# 1-Schematic_Final_project.net
KiCad netlist of a schematic drawn in EasyEDA
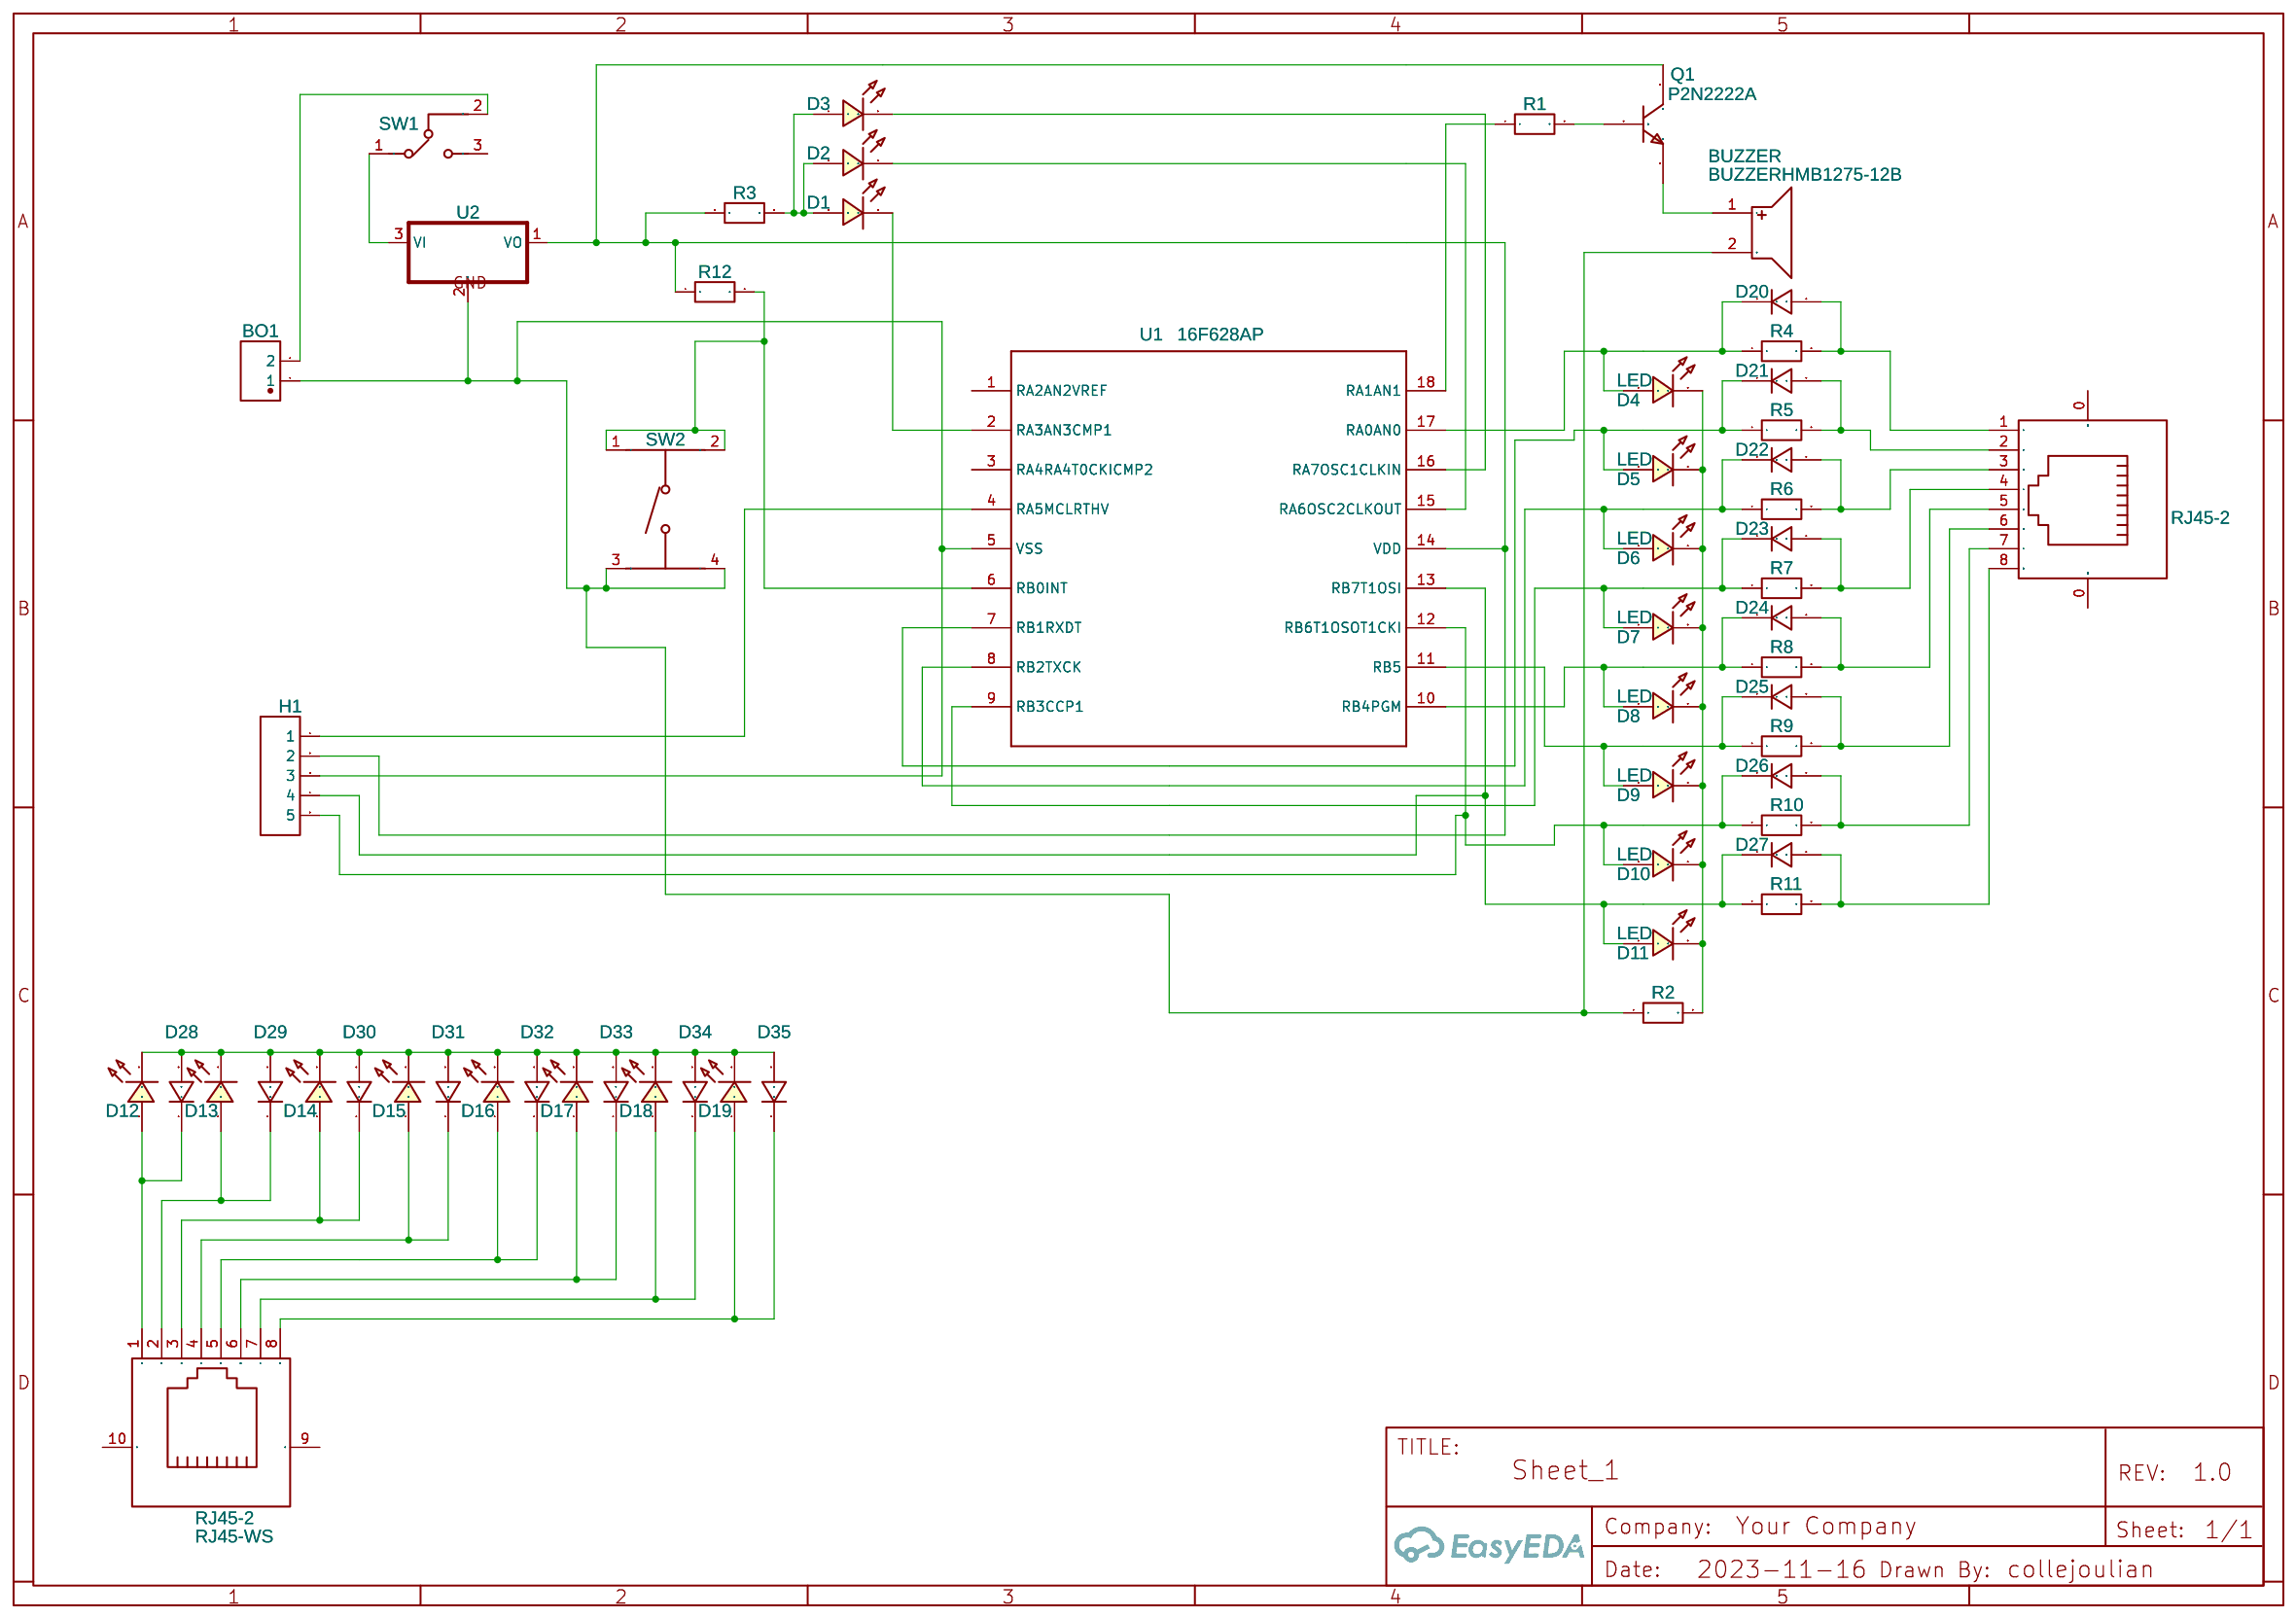
[diagram p0: schematic sheet]

(export (version "E")
  (design (tool "Eeschema 10.0.6"))
  (components
    (comp (ref "BO1")
      (value "BV-2P-5mm")
      (fields
        (field (name "Manufacturer Part") "KF301-5.0-2P")
        (field (name "Manufacturer") "Cixi Kefa Elec")
      )
      (libsource (lib "") (part "Bornier A Vis 2P - 5mm"))
    )
    (comp (ref "BUZZER")
      (value "BUZZERHMB1275-12B")
      (fields (field (name "Manufacturer Part") "buzzerHMB1275-12B") (field (name "Manufacturer") "HNDZ"))
      (libsource (lib "") (part "BUZZERHMB1275-12B"))
    )
    (comp (ref "D1")
      (value "D1")
      (fields
        (field (name "Manufacturer Part") "204-10SDRD/S530-A3-L")
        (field (name "Manufacturer") "EVERLIGHT(台湾亿光)")
      )
      (libsource (lib "") (part "LED-TH-3mm_R_1"))
    )
    (comp (ref "D2")
      (value "D2")
      (fields
        (field (name "Manufacturer Part") "204-10SDRD/S530-A3-L")
        (field (name "Manufacturer") "EVERLIGHT(台湾亿光)")
      )
      (libsource (lib "") (part "LED-TH-3mm_R_1"))
    )
    (comp (ref "D3")
      (value "D3")
      (fields
        (field (name "Manufacturer Part") "204-10SDRD/S530-A3-L")
        (field (name "Manufacturer") "EVERLIGHT(台湾亿光)")
      )
      (libsource (lib "") (part "LED-TH-3mm_R_1"))
    )
    (comp (ref "D4")
      (value "LED")
      (fields
        (field (name "Manufacturer Part") "204-10SDRD/S530-A3-L")
        (field (name "Manufacturer") "EVERLIGHT(台湾亿光)")
      )
      (libsource (lib "") (part "LED-TH-3mm_R_1"))
    )
    (comp (ref "D5")
      (value "LED")
      (fields
        (field (name "Manufacturer Part") "204-10SDRD/S530-A3-L")
        (field (name "Manufacturer") "EVERLIGHT(台湾亿光)")
      )
      (libsource (lib "") (part "LED-TH-3mm_R_1"))
    )
    (comp (ref "D6")
      (value "LED")
      (fields
        (field (name "Manufacturer Part") "204-10SDRD/S530-A3-L")
        (field (name "Manufacturer") "EVERLIGHT(台湾亿光)")
      )
      (libsource (lib "") (part "LED-TH-3mm_R_1"))
    )
    (comp (ref "D7")
      (value "LED")
      (fields
        (field (name "Manufacturer Part") "204-10SDRD/S530-A3-L")
        (field (name "Manufacturer") "EVERLIGHT(台湾亿光)")
      )
      (libsource (lib "") (part "LED-TH-3mm_R_1"))
    )
    (comp (ref "D8")
      (value "LED")
      (fields
        (field (name "Manufacturer Part") "204-10SDRD/S530-A3-L")
        (field (name "Manufacturer") "EVERLIGHT(台湾亿光)")
      )
      (libsource (lib "") (part "LED-TH-3mm_R_1"))
    )
    (comp (ref "D9")
      (value "LED")
      (fields
        (field (name "Manufacturer Part") "204-10SDRD/S530-A3-L")
        (field (name "Manufacturer") "EVERLIGHT(台湾亿光)")
      )
      (libsource (lib "") (part "LED-TH-3mm_R_1"))
    )
    (comp (ref "D10")
      (value "LED")
      (fields
        (field (name "Manufacturer Part") "204-10SDRD/S530-A3-L")
        (field (name "Manufacturer") "EVERLIGHT(台湾亿光)")
      )
      (libsource (lib "") (part "LED-TH-3mm_R_1"))
    )
    (comp (ref "D11")
      (value "LED")
      (fields
        (field (name "Manufacturer Part") "204-10SDRD/S530-A3-L")
        (field (name "Manufacturer") "EVERLIGHT(台湾亿光)")
      )
      (libsource (lib "") (part "LED-TH-3mm_R_1"))
    )
    (comp (ref "D12")
      (value "D12")
      (fields
        (field (name "Manufacturer Part") "204-10SDRD/S530-A3-L")
        (field (name "Manufacturer") "EVERLIGHT(台湾亿光)")
      )
      (libsource (lib "") (part "LED-TH-3mm_R"))
    )
    (comp (ref "D13")
      (value "D13")
      (fields
        (field (name "Manufacturer Part") "204-10SDRD/S530-A3-L")
        (field (name "Manufacturer") "EVERLIGHT(台湾亿光)")
      )
      (libsource (lib "") (part "LED-TH-3mm_R"))
    )
    (comp (ref "D14")
      (value "D14")
      (fields
        (field (name "Manufacturer Part") "204-10SDRD/S530-A3-L")
        (field (name "Manufacturer") "EVERLIGHT(台湾亿光)")
      )
      (libsource (lib "") (part "LED-TH-3mm_R"))
    )
    (comp (ref "D15")
      (value "D15")
      (fields
        (field (name "Manufacturer Part") "204-10SDRD/S530-A3-L")
        (field (name "Manufacturer") "EVERLIGHT(台湾亿光)")
      )
      (libsource (lib "") (part "LED-TH-3mm_R"))
    )
    (comp (ref "D16")
      (value "D16")
      (fields
        (field (name "Manufacturer Part") "204-10SDRD/S530-A3-L")
        (field (name "Manufacturer") "EVERLIGHT(台湾亿光)")
      )
      (libsource (lib "") (part "LED-TH-3mm_R"))
    )
    (comp (ref "D17")
      (value "D17")
      (fields
        (field (name "Manufacturer Part") "204-10SDRD/S530-A3-L")
        (field (name "Manufacturer") "EVERLIGHT(台湾亿光)")
      )
      (libsource (lib "") (part "LED-TH-3mm_R"))
    )
    (comp (ref "D18")
      (value "D18")
      (fields
        (field (name "Manufacturer Part") "204-10SDRD/S530-A3-L")
        (field (name "Manufacturer") "EVERLIGHT(台湾亿光)")
      )
      (libsource (lib "") (part "LED-TH-3mm_R"))
    )
    (comp (ref "D19")
      (value "D19")
      (fields
        (field (name "Manufacturer Part") "204-10SDRD/S530-A3-L")
        (field (name "Manufacturer") "EVERLIGHT(台湾亿光)")
      )
      (libsource (lib "") (part "LED-TH-3mm_R"))
    )
    (comp (ref "D20")
      (value "D")
      (fields (field (name "Manufacturer Part") "1N4148") (field (name "Manufacturer") "STMicroelectronics"))
      (libsource (lib "") (part "1N4148"))
    )
    (comp (ref "D21")
      (value "D")
      (fields (field (name "Manufacturer Part") "1N4148") (field (name "Manufacturer") "STMicroelectronics"))
      (libsource (lib "") (part "1N4148"))
    )
    (comp (ref "D22")
      (value "D")
      (fields (field (name "Manufacturer Part") "1N4148") (field (name "Manufacturer") "STMicroelectronics"))
      (libsource (lib "") (part "1N4148"))
    )
    (comp (ref "D23")
      (value "D")
      (fields (field (name "Manufacturer Part") "1N4148") (field (name "Manufacturer") "STMicroelectronics"))
      (libsource (lib "") (part "1N4148"))
    )
    (comp (ref "D24")
      (value "D")
      (fields (field (name "Manufacturer Part") "1N4148") (field (name "Manufacturer") "STMicroelectronics"))
      (libsource (lib "") (part "1N4148"))
    )
    (comp (ref "D25")
      (value "D")
      (fields (field (name "Manufacturer Part") "1N4148") (field (name "Manufacturer") "STMicroelectronics"))
      (libsource (lib "") (part "1N4148"))
    )
    (comp (ref "D26")
      (value "D")
      (fields (field (name "Manufacturer Part") "1N4148") (field (name "Manufacturer") "STMicroelectronics"))
      (libsource (lib "") (part "1N4148"))
    )
    (comp (ref "D27")
      (value "D")
      (fields (field (name "Manufacturer Part") "1N4148") (field (name "Manufacturer") "STMicroelectronics"))
      (libsource (lib "") (part "1N4148"))
    )
    (comp (ref "D28")
      (value "D28")
      (fields (field (name "Manufacturer Part") "1N4148") (field (name "Manufacturer") "STMicroelectronics"))
      (libsource (lib "") (part "1N4148_1"))
    )
    (comp (ref "D29")
      (value "D29")
      (fields (field (name "Manufacturer Part") "1N4148") (field (name "Manufacturer") "STMicroelectronics"))
      (libsource (lib "") (part "1N4148_1"))
    )
    (comp (ref "D30")
      (value "D30")
      (fields (field (name "Manufacturer Part") "1N4148") (field (name "Manufacturer") "STMicroelectronics"))
      (libsource (lib "") (part "1N4148_1"))
    )
    (comp (ref "D31")
      (value "D31")
      (fields (field (name "Manufacturer Part") "1N4148") (field (name "Manufacturer") "STMicroelectronics"))
      (libsource (lib "") (part "1N4148_1"))
    )
    (comp (ref "D32")
      (value "D32")
      (fields (field (name "Manufacturer Part") "1N4148") (field (name "Manufacturer") "STMicroelectronics"))
      (libsource (lib "") (part "1N4148_1"))
    )
    (comp (ref "D33")
      (value "D33")
      (fields (field (name "Manufacturer Part") "1N4148") (field (name "Manufacturer") "STMicroelectronics"))
      (libsource (lib "") (part "1N4148_1"))
    )
    (comp (ref "D34")
      (value "D34")
      (fields (field (name "Manufacturer Part") "1N4148") (field (name "Manufacturer") "STMicroelectronics"))
      (libsource (lib "") (part "1N4148_1"))
    )
    (comp (ref "D35")
      (value "D35")
      (fields (field (name "Manufacturer Part") "1N4148") (field (name "Manufacturer") "STMicroelectronics"))
      (libsource (lib "") (part "1N4148_1"))
    )
    (comp (ref "H1")
      (value "1z2")
      (fields (field (name "Manufacturer Part") "2.54-1*5P母") (field (name "Manufacturer") "BOOMELE(博穆精密)"))
      (libsource (lib "") (part "Header-Female-2.54_1x5"))
    )
    (comp (ref "Q1") (value "P2N2222A") (libsource (lib "") (part "P2N2222A")))
    (comp (ref "R1") (value "1k") (libsource (lib "") (part "R_AXIAL-0.3_EU")))
    (comp (ref "R2") (value "1k") (libsource (lib "") (part "R_AXIAL-0.3_EU")))
    (comp (ref "R3") (value "1k") (libsource (lib "") (part "R_AXIAL-0.3_EU")))
    (comp (ref "R4") (value "1k") (libsource (lib "") (part "R_AXIAL-0.3_EU")))
    (comp (ref "R5") (value "1k") (libsource (lib "") (part "R_AXIAL-0.3_EU")))
    (comp (ref "R6") (value "1k") (libsource (lib "") (part "R_AXIAL-0.3_EU")))
    (comp (ref "R7") (value "1k") (libsource (lib "") (part "R_AXIAL-0.3_EU")))
    (comp (ref "R8") (value "1k") (libsource (lib "") (part "R_AXIAL-0.3_EU")))
    (comp (ref "R9") (value "1k") (libsource (lib "") (part "R_AXIAL-0.3_EU")))
    (comp (ref "R10") (value "1k") (libsource (lib "") (part "R_AXIAL-0.3_EU")))
    (comp (ref "R11") (value "1k") (libsource (lib "") (part "R_AXIAL-0.3_EU")))
    (comp (ref "R12") (value "1k") (libsource (lib "") (part "R_AXIAL-0.3_EU")))
    (comp (ref "RJ45")
      (value "RJ45-2")
      (fields (field (name "Manufacturer Part") "DS1128-04-S8B8P-X") (field (name "Manufacturer") "CONNFLY"))
      (libsource (lib "") (part "DS1128-04-S8B8P-X"))
    )
    (comp (ref "RJ45-2")
      (value "RJ45-WS")
      (fields
        (field (name "Manufacturer Part") "FRJ45004-1100K6K02C0")
        (field (name "Manufacturer") "TXGA(特思嘉)")
      )
      (libsource (lib "") (part "FRJ45004-1100K6K02C0"))
    )
    (comp (ref "SW1")
      (value "SW1")
      (fields (field (name "Manufacturer Part") "1101M2S3CQE2") (field (name "Manufacturer") "C&K"))
      (libsource (lib "") (part "1101M2S3CQE2"))
    )
    (comp (ref "SW2")
      (value "TS-1102-5016")
      (fields (field (name "Manufacturer") "SOFNG(硕方)"))
      (libsource (lib "") (part "TS-1102-5016"))
    )
    (comp (ref "U1") (value "16F628AP") (libsource (lib "") (part "16F628AP")))
    (comp (ref "U2") (value "7805L") (libsource (lib "") (part "7805L")))
  )
  (nets
    (net (code "1") (name "Net-(BO1-Pad2)") (class "Default")
      (node (ref "BO1") (pin "2") (pinfunction "2_2") (pintype "unspecified"))
      (node (ref "SW1") (pin "2") (pinfunction "2_2") (pintype "unspecified"))
    )
    (net (code "2") (name "Net-(D1-Pad1)") (class "Default")
      (node (ref "D1") (pin "1") (pinfunction "1_1") (pintype "unspecified"))
      (node (ref "D2") (pin "1") (pinfunction "1_1") (pintype "unspecified"))
      (node (ref "D3") (pin "1") (pinfunction "1_1") (pintype "unspecified"))
      (node (ref "R3") (pin "2") (pinfunction "2_2") (pintype "unspecified"))
    )
    (net (code "3") (name "Net-(D10-Pad2)") (class "Default")
      (node (ref "D10") (pin "2") (pinfunction "2_2") (pintype "unspecified"))
      (node (ref "D11") (pin "2") (pinfunction "2_2") (pintype "unspecified"))
      (node (ref "D4") (pin "2") (pinfunction "2_2") (pintype "unspecified"))
      (node (ref "D5") (pin "2") (pinfunction "2_2") (pintype "unspecified"))
      (node (ref "D6") (pin "2") (pinfunction "2_2") (pintype "unspecified"))
      (node (ref "D7") (pin "2") (pinfunction "2_2") (pintype "unspecified"))
      (node (ref "D8") (pin "2") (pinfunction "2_2") (pintype "unspecified"))
      (node (ref "D9") (pin "2") (pinfunction "2_2") (pintype "unspecified"))
      (node (ref "R2") (pin "2") (pinfunction "2_2") (pintype "unspecified"))
    )
    (net (code "4") (name "Net-(D12-Pad1)") (class "Default")
      (node (ref "D12") (pin "1") (pinfunction "1_1") (pintype "unspecified"))
      (node (ref "D28") (pin "1") (pinfunction "1_1") (pintype "unspecified"))
      (node (ref "RJ45-2") (pin "1") (pinfunction "1_1") (pintype "unspecified"))
    )
    (net (code "5") (name "Net-(D12-Pad2)") (class "Default")
      (node (ref "D12") (pin "2") (pinfunction "2_2") (pintype "unspecified"))
      (node (ref "D13") (pin "2") (pinfunction "2_2") (pintype "unspecified"))
      (node (ref "D14") (pin "2") (pinfunction "2_2") (pintype "unspecified"))
      (node (ref "D15") (pin "2") (pinfunction "2_2") (pintype "unspecified"))
      (node (ref "D16") (pin "2") (pinfunction "2_2") (pintype "unspecified"))
      (node (ref "D17") (pin "2") (pinfunction "2_2") (pintype "unspecified"))
      (node (ref "D18") (pin "2") (pinfunction "2_2") (pintype "unspecified"))
      (node (ref "D19") (pin "2") (pinfunction "2_2") (pintype "unspecified"))
      (node (ref "D28") (pin "2") (pinfunction "2_2") (pintype "unspecified"))
      (node (ref "D29") (pin "2") (pinfunction "2_2") (pintype "unspecified"))
      (node (ref "D30") (pin "2") (pinfunction "2_2") (pintype "unspecified"))
      (node (ref "D31") (pin "2") (pinfunction "2_2") (pintype "unspecified"))
      (node (ref "D32") (pin "2") (pinfunction "2_2") (pintype "unspecified"))
      (node (ref "D33") (pin "2") (pinfunction "2_2") (pintype "unspecified"))
      (node (ref "D34") (pin "2") (pinfunction "2_2") (pintype "unspecified"))
      (node (ref "D35") (pin "2") (pinfunction "2_2") (pintype "unspecified"))
    )
    (net (code "6") (name "Net-(D13-Pad1)") (class "Default")
      (node (ref "D13") (pin "1") (pinfunction "1_1") (pintype "unspecified"))
      (node (ref "D29") (pin "1") (pinfunction "1_1") (pintype "unspecified"))
      (node (ref "RJ45-2") (pin "2") (pinfunction "2_2") (pintype "unspecified"))
    )
    (net (code "7") (name "Net-(D14-Pad1)") (class "Default")
      (node (ref "D14") (pin "1") (pinfunction "1_1") (pintype "unspecified"))
      (node (ref "D30") (pin "1") (pinfunction "1_1") (pintype "unspecified"))
      (node (ref "RJ45-2") (pin "3") (pinfunction "3_3") (pintype "unspecified"))
    )
    (net (code "8") (name "Net-(D15-Pad1)") (class "Default")
      (node (ref "D15") (pin "1") (pinfunction "1_1") (pintype "unspecified"))
      (node (ref "D31") (pin "1") (pinfunction "1_1") (pintype "unspecified"))
      (node (ref "RJ45-2") (pin "4") (pinfunction "4_4") (pintype "unspecified"))
    )
    (net (code "9") (name "Net-(D16-Pad1)") (class "Default")
      (node (ref "D16") (pin "1") (pinfunction "1_1") (pintype "unspecified"))
      (node (ref "D32") (pin "1") (pinfunction "1_1") (pintype "unspecified"))
      (node (ref "RJ45-2") (pin "5") (pinfunction "5_5") (pintype "unspecified"))
    )
    (net (code "10") (name "Net-(D17-Pad1)") (class "Default")
      (node (ref "D17") (pin "1") (pinfunction "1_1") (pintype "unspecified"))
      (node (ref "D33") (pin "1") (pinfunction "1_1") (pintype "unspecified"))
      (node (ref "RJ45-2") (pin "6") (pinfunction "6_6") (pintype "unspecified"))
    )
    (net (code "11") (name "Net-(D18-Pad1)") (class "Default")
      (node (ref "D18") (pin "1") (pinfunction "1_1") (pintype "unspecified"))
      (node (ref "D34") (pin "1") (pinfunction "1_1") (pintype "unspecified"))
      (node (ref "RJ45-2") (pin "7") (pinfunction "7_7") (pintype "unspecified"))
    )
    (net (code "12") (name "Net-(D19-Pad1)") (class "Default")
      (node (ref "D19") (pin "1") (pinfunction "1_1") (pintype "unspecified"))
      (node (ref "D35") (pin "1") (pinfunction "1_1") (pintype "unspecified"))
      (node (ref "RJ45-2") (pin "8") (pinfunction "8_8") (pintype "unspecified"))
    )
    (net (code "13") (name "Net-(D20-Pad2)") (class "Default")
      (node (ref "D20") (pin "2") (pinfunction "2_2") (pintype "unspecified"))
      (node (ref "R4") (pin "2") (pinfunction "2_2") (pintype "unspecified"))
      (node (ref "RJ45") (pin "1") (pinfunction "1_1") (pintype "unspecified"))
    )
    (net (code "14") (name "Net-(D21-Pad2)") (class "Default")
      (node (ref "D21") (pin "2") (pinfunction "2_2") (pintype "unspecified"))
      (node (ref "R5") (pin "2") (pinfunction "2_2") (pintype "unspecified"))
      (node (ref "RJ45") (pin "2") (pinfunction "2_2") (pintype "unspecified"))
    )
    (net (code "15") (name "Net-(D22-Pad2)") (class "Default")
      (node (ref "D22") (pin "2") (pinfunction "2_2") (pintype "unspecified"))
      (node (ref "R6") (pin "2") (pinfunction "2_2") (pintype "unspecified"))
      (node (ref "RJ45") (pin "3") (pinfunction "3_3") (pintype "unspecified"))
    )
    (net (code "16") (name "Net-(D23-Pad2)") (class "Default")
      (node (ref "D23") (pin "2") (pinfunction "2_2") (pintype "unspecified"))
      (node (ref "R7") (pin "2") (pinfunction "2_2") (pintype "unspecified"))
      (node (ref "RJ45") (pin "4") (pinfunction "4_4") (pintype "unspecified"))
    )
    (net (code "17") (name "Net-(D24-Pad2)") (class "Default")
      (node (ref "D24") (pin "2") (pinfunction "2_2") (pintype "unspecified"))
      (node (ref "R8") (pin "2") (pinfunction "2_2") (pintype "unspecified"))
      (node (ref "RJ45") (pin "5") (pinfunction "5_5") (pintype "unspecified"))
    )
    (net (code "18") (name "Net-(D25-Pad2)") (class "Default")
      (node (ref "D25") (pin "2") (pinfunction "2_2") (pintype "unspecified"))
      (node (ref "R9") (pin "2") (pinfunction "2_2") (pintype "unspecified"))
      (node (ref "RJ45") (pin "6") (pinfunction "6_6") (pintype "unspecified"))
    )
    (net (code "19") (name "Net-(D26-Pad2)") (class "Default")
      (node (ref "D26") (pin "2") (pinfunction "2_2") (pintype "unspecified"))
      (node (ref "R10") (pin "2") (pinfunction "2_2") (pintype "unspecified"))
      (node (ref "RJ45") (pin "7") (pinfunction "7_7") (pintype "unspecified"))
    )
    (net (code "20") (name "Net-(D27-Pad2)") (class "Default")
      (node (ref "D27") (pin "2") (pinfunction "2_2") (pintype "unspecified"))
      (node (ref "R11") (pin "2") (pinfunction "2_2") (pintype "unspecified"))
      (node (ref "RJ45") (pin "8") (pinfunction "8_8") (pintype "unspecified"))
    )
    (net (code "21") (name "Net-(Q1-B)") (class "Default")
      (node (ref "Q1") (pin "2") (pinfunction "B_2") (pintype "unspecified"))
      (node (ref "R1") (pin "2") (pinfunction "2_2") (pintype "unspecified"))
    )
    (net (code "22") (name "Net-(Q1-C)") (class "Default")
      (node (ref "H1") (pin "2") (pinfunction "2_2") (pintype "input"))
      (node (ref "Q1") (pin "1") (pinfunction "C_1") (pintype "unspecified"))
      (node (ref "R12") (pin "1") (pinfunction "1_1") (pintype "unspecified"))
      (node (ref "R3") (pin "1") (pinfunction "1_1") (pintype "unspecified"))
      (node (ref "U1") (pin "14") (pinfunction "VDD_14") (pintype "passive"))
      (node (ref "U2") (pin "1") (pinfunction "VO_1") (pintype "unspecified"))
    )
    (net (code "23") (name "Net-(Q1-E)") (class "Default")
      (node (ref "BUZZER") (pin "1") (pinfunction "1_1") (pintype "unspecified"))
      (node (ref "Q1") (pin "3") (pinfunction "E_3") (pintype "unspecified"))
    )
    (net (code "24") (name "Net-(U1-RA0AN0)") (class "Default")
      (node (ref "D20") (pin "1") (pinfunction "1_1") (pintype "unspecified"))
      (node (ref "D4") (pin "1") (pinfunction "1_1") (pintype "unspecified"))
      (node (ref "R4") (pin "1") (pinfunction "1_1") (pintype "unspecified"))
      (node (ref "U1") (pin "17") (pinfunction "RA0AN0_17") (pintype "unspecified"))
    )
    (net (code "25") (name "Net-(U1-RA1AN1)") (class "Default")
      (node (ref "R1") (pin "1") (pinfunction "1_1") (pintype "unspecified"))
      (node (ref "U1") (pin "18") (pinfunction "RA1AN1_18") (pintype "unspecified"))
    )
    (net (code "26") (name "Net-(U1-RA3AN3CMP1)") (class "Default")
      (node (ref "D1") (pin "2") (pinfunction "2_2") (pintype "unspecified"))
      (node (ref "U1") (pin "2") (pinfunction "RA3AN3CMP1_2") (pintype "unspecified"))
    )
    (net (code "27") (name "Net-(U1-RA5MCLRTHV)") (class "Default")
      (node (ref "H1") (pin "1") (pinfunction "1_1") (pintype "input"))
      (node (ref "U1") (pin "4") (pinfunction "RA5MCLRTHV_4") (pintype "input"))
    )
    (net (code "28") (name "Net-(U1-RA6OSC2CLKOUT)") (class "Default")
      (node (ref "D2") (pin "2") (pinfunction "2_2") (pintype "unspecified"))
      (node (ref "U1") (pin "15") (pinfunction "RA6OSC2CLKOUT_15") (pintype "unspecified"))
    )
    (net (code "29") (name "Net-(U1-RA7OSC1CLKIN)") (class "Default")
      (node (ref "D3") (pin "2") (pinfunction "2_2") (pintype "unspecified"))
      (node (ref "U1") (pin "16") (pinfunction "RA7OSC1CLKIN_16") (pintype "unspecified"))
    )
    (net (code "30") (name "Net-(U1-RB0INT)") (class "Default")
      (node (ref "R12") (pin "2") (pinfunction "2_2") (pintype "unspecified"))
      (node (ref "SW2") (pin "1") (pinfunction "1_1") (pintype "unspecified"))
      (node (ref "SW2") (pin "2") (pinfunction "2_2") (pintype "unspecified"))
      (node (ref "U1") (pin "6") (pinfunction "RB0INT_6") (pintype "unspecified"))
    )
    (net (code "31") (name "Net-(U1-RB1RXDT)") (class "Default")
      (node (ref "D21") (pin "1") (pinfunction "1_1") (pintype "unspecified"))
      (node (ref "D5") (pin "1") (pinfunction "1_1") (pintype "unspecified"))
      (node (ref "R5") (pin "1") (pinfunction "1_1") (pintype "unspecified"))
      (node (ref "U1") (pin "7") (pinfunction "RB1RXDT_7") (pintype "unspecified"))
    )
    (net (code "32") (name "Net-(U1-RB2TXCK)") (class "Default")
      (node (ref "D22") (pin "1") (pinfunction "1_1") (pintype "unspecified"))
      (node (ref "D6") (pin "1") (pinfunction "1_1") (pintype "unspecified"))
      (node (ref "R6") (pin "1") (pinfunction "1_1") (pintype "unspecified"))
      (node (ref "U1") (pin "8") (pinfunction "RB2TXCK_8") (pintype "unspecified"))
    )
    (net (code "33") (name "Net-(U1-RB3CCP1)") (class "Default")
      (node (ref "D23") (pin "1") (pinfunction "1_1") (pintype "unspecified"))
      (node (ref "D7") (pin "1") (pinfunction "1_1") (pintype "unspecified"))
      (node (ref "R7") (pin "1") (pinfunction "1_1") (pintype "unspecified"))
      (node (ref "U1") (pin "9") (pinfunction "RB3CCP1_9") (pintype "unspecified"))
    )
    (net (code "34") (name "Net-(U1-RB4PGM)") (class "Default")
      (node (ref "D24") (pin "1") (pinfunction "1_1") (pintype "unspecified"))
      (node (ref "D8") (pin "1") (pinfunction "1_1") (pintype "unspecified"))
      (node (ref "R8") (pin "1") (pinfunction "1_1") (pintype "unspecified"))
      (node (ref "U1") (pin "10") (pinfunction "RB4PGM_10") (pintype "unspecified"))
    )
    (net (code "35") (name "Net-(U1-RB5)") (class "Default")
      (node (ref "D25") (pin "1") (pinfunction "1_1") (pintype "unspecified"))
      (node (ref "D9") (pin "1") (pinfunction "1_1") (pintype "unspecified"))
      (node (ref "R9") (pin "1") (pinfunction "1_1") (pintype "unspecified"))
      (node (ref "U1") (pin "11") (pinfunction "RB5_11") (pintype "unspecified"))
    )
    (net (code "36") (name "Net-(U1-RB6T1OSOT1CKI)") (class "Default")
      (node (ref "D10") (pin "1") (pinfunction "1_1") (pintype "unspecified"))
      (node (ref "D26") (pin "1") (pinfunction "1_1") (pintype "unspecified"))
      (node (ref "H1") (pin "5") (pinfunction "5_5") (pintype "input"))
      (node (ref "R10") (pin "1") (pinfunction "1_1") (pintype "unspecified"))
      (node (ref "U1") (pin "12") (pinfunction "RB6T1OSOT1CKI_12") (pintype "unspecified"))
    )
    (net (code "37") (name "Net-(U1-RB7T1OSI)") (class "Default")
      (node (ref "D11") (pin "1") (pinfunction "1_1") (pintype "unspecified"))
      (node (ref "D27") (pin "1") (pinfunction "1_1") (pintype "unspecified"))
      (node (ref "H1") (pin "4") (pinfunction "4_4") (pintype "input"))
      (node (ref "R11") (pin "1") (pinfunction "1_1") (pintype "unspecified"))
      (node (ref "U1") (pin "13") (pinfunction "RB7T1OSI_13") (pintype "unspecified"))
    )
    (net (code "38") (name "Net-(U1-VSS)") (class "Default")
      (node (ref "BO1") (pin "1") (pinfunction "1_1") (pintype "unspecified"))
      (node (ref "BUZZER") (pin "2") (pinfunction "2_2") (pintype "unspecified"))
      (node (ref "H1") (pin "3") (pinfunction "3_3") (pintype "input"))
      (node (ref "R2") (pin "1") (pinfunction "1_1") (pintype "unspecified"))
      (node (ref "SW2") (pin "3") (pinfunction "3_3") (pintype "unspecified"))
      (node (ref "SW2") (pin "4") (pinfunction "4_4") (pintype "unspecified"))
      (node (ref "U1") (pin "5") (pinfunction "VSS_5") (pintype "passive"))
      (node (ref "U2") (pin "2") (pinfunction "GND_2") (pintype "unspecified"))
    )
    (net (code "39") (name "Net-(U2-VI)") (class "Default")
      (node (ref "SW1") (pin "1") (pinfunction "1_1") (pintype "unspecified"))
      (node (ref "U2") (pin "3") (pinfunction "VI_3") (pintype "input"))
    )
    (net (code "40") (name "unconnected-(RJ45-2-EH-Pad9)") (class "Default")
      (node (ref "RJ45-2") (pin "9") (pinfunction "EH_9") (pintype "unspecified"))
    )
    (net (code "41") (name "unconnected-(RJ45-2-EH-Pad10)") (class "Default")
      (node (ref "RJ45-2") (pin "10") (pinfunction "EH_10") (pintype "unspecified"))
    )
    (net (code "42") (name "unconnected-(RJ45-SHIELD-Pad0)") (class "Default")
      (node (ref "RJ45") (pin "0") (pinfunction "SHIELD_0") (pintype "unspecified"))
    )
    (net (code "43") (name "unconnected-(RJ45-SHIELD-Pad0)_1") (class "Default")
      (node (ref "RJ45") (pin "0") (pinfunction "SHIELD_0") (pintype "unspecified"))
    )
    (net (code "44") (name "unconnected-(SW1-Pad3)") (class "Default")
      (node (ref "SW1") (pin "3") (pinfunction "3_3") (pintype "unspecified"))
    )
    (net (code "45") (name "unconnected-(U1-RA2AN2VREF-Pad1)") (class "Default")
      (node (ref "U1") (pin "1") (pinfunction "RA2AN2VREF_1") (pintype "unspecified"))
    )
    (net (code "46") (name "unconnected-(U1-RA4RA4T0CKICMP2-Pad3)") (class "Default")
      (node (ref "U1") (pin "3") (pinfunction "RA4RA4T0CKICMP2_3") (pintype "unspecified"))
    )
  )
)
